# Power.net
KiCad netlist of a schematic drawn in Altium Designer
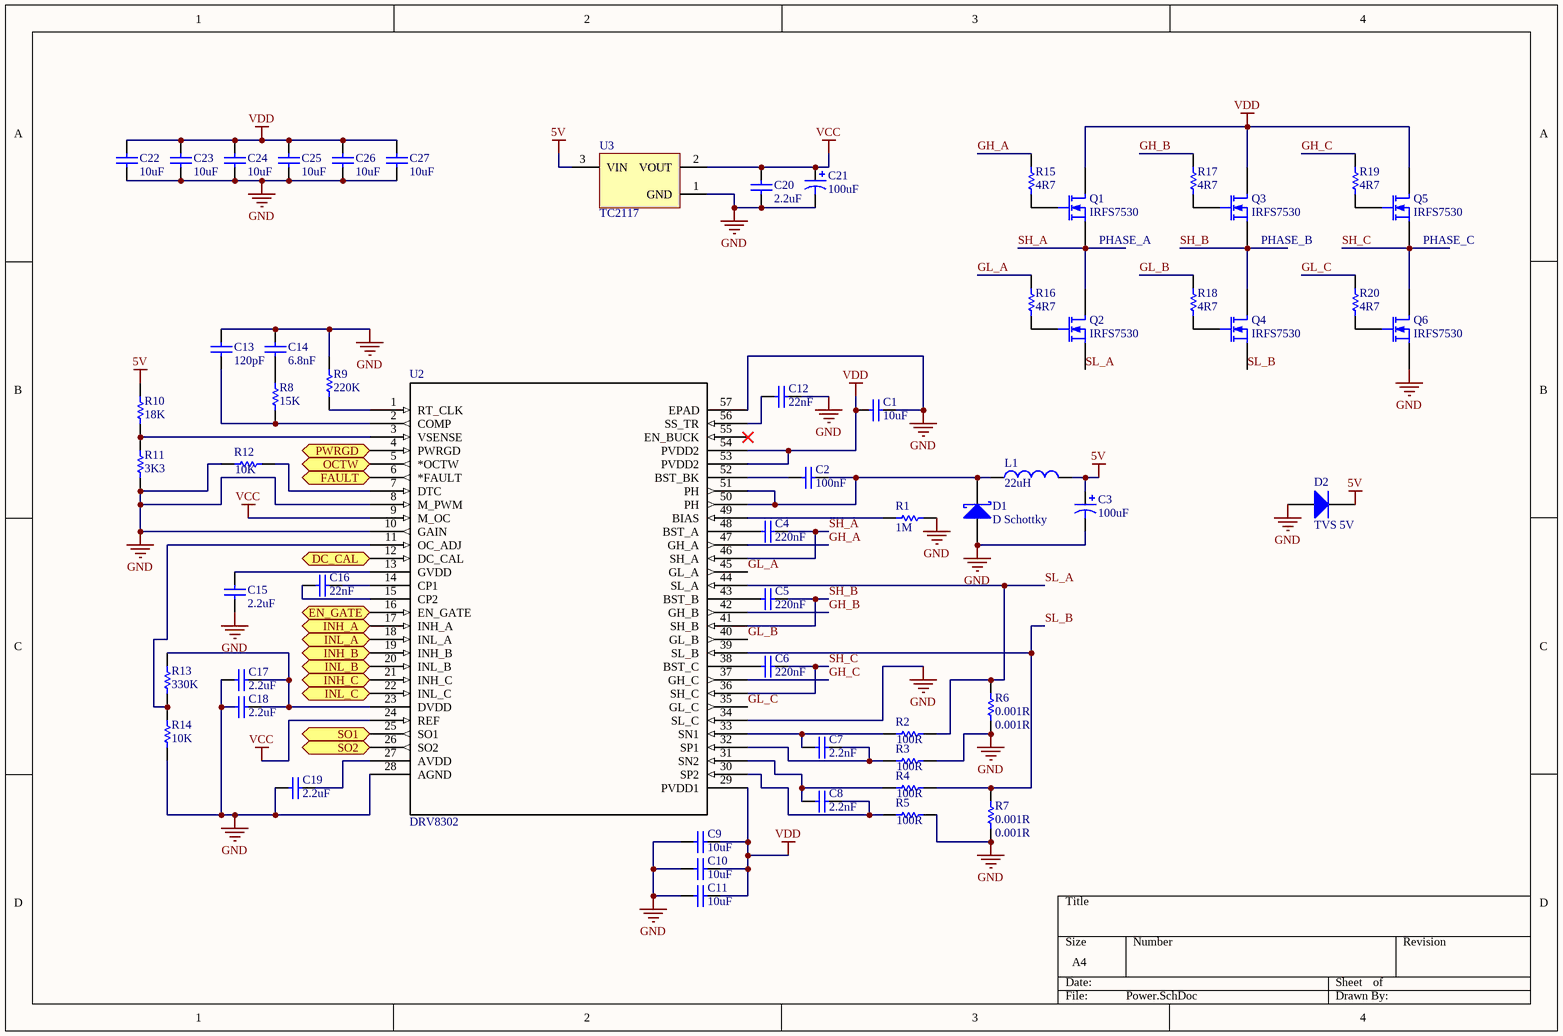
[diagram p0: Power.SchDoc]

(export (version "E")
  (design (tool "Eeschema 10.0.6"))
  (components
    (comp (ref "C1")
      (value "10uF")
      (footprint "CAPC1206(3216)190_M")
      (description "CAP 10uF 50V Â±10% 1206 (3216 Metric) Thickness 1.9mm SMD")
      (fields (field (name "TOLERANCE") "Â±10%"))
      (libsource (lib "Altium Content Vault") (part "CAP"))
    )
    (comp (ref "C2")
      (value "100nF")
      (footprint "CAPC0603(1608)100_N")
      (description "CAP 100nF 50V Â±5% 0603 (1608 Metric) Thickness 1mm SMD")
      (fields (field (name "TOLERANCE") "Â±5%"))
      (libsource (lib "Altium Content Vault") (part "CMP-1035-02591-1"))
    )
    (comp (ref "C3")
      (value "100uF")
      (footprint "AVX-CAPC7343_V")
      (description "Capacitor, Tantalum, 220uF 10% 10V MCCT-D (7343-31)")
      (fields (field (name "PARTNUMBER") "TAJD227K010R") (field (name "MANUFACTURER") "AVX"))
      (libsource (lib "Altium Content Vault") (part "CMP-0279-00002-1"))
    )
    (comp (ref "C4")
      (value "220nF")
      (footprint "CAPC0805(2012)145_M")
      (description "CAP 220nF 25V Â±5% 0805 (2012 Metric) Thickness 1.45mm SMD")
      (fields (field (name "TOLERANCE") "Â±5%"))
      (libsource (lib "Altium Content Vault") (part "CMP-1036-04540-1"))
    )
    (comp (ref "C5")
      (value "220nF")
      (footprint "CAPC0805(2012)145_M")
      (description "CAP 220nF 25V Â±5% 0805 (2012 Metric) Thickness 1.45mm SMD")
      (fields (field (name "TOLERANCE") "Â±5%"))
      (libsource (lib "Altium Content Vault") (part "CMP-1036-04540-1"))
    )
    (comp (ref "C6")
      (value "220nF")
      (footprint "CAPC0805(2012)145_M")
      (description "CAP 220nF 25V Â±5% 0805 (2012 Metric) Thickness 1.45mm SMD")
      (fields (field (name "TOLERANCE") "Â±5%"))
      (libsource (lib "Altium Content Vault") (part "CMP-1036-04540-1"))
    )
    (comp (ref "C7")
      (value "2.2nF")
      (footprint "CAPC0603(1608)100_N")
      (description "CAP 2.2nF 50V Â±1% 0603 (1608 Metric) Thickness 1mm SMD")
      (fields (field (name "TOLERANCE") "Â±1%"))
      (libsource (lib "Altium Content Vault") (part "CMP-1035-02036-1"))
    )
    (comp (ref "C8")
      (value "2.2nF")
      (footprint "CAPC0603(1608)100_N")
      (description "CAP 2.2nF 50V Â±1% 0603 (1608 Metric) Thickness 1mm SMD")
      (fields (field (name "TOLERANCE") "Â±1%"))
      (libsource (lib "Altium Content Vault") (part "CMP-1035-02036-1"))
    )
    (comp (ref "C9")
      (value "10uF")
      (footprint "CAPC1206(3216)190_M")
      (description "CAP 10uF 50V Â±10% 1206 (3216 Metric) Thickness 1.9mm SMD")
      (fields (field (name "TOLERANCE") "Â±10%"))
      (libsource (lib "Altium Content Vault") (part "CAP"))
    )
    (comp (ref "C10")
      (value "10uF")
      (footprint "CAPC1206(3216)190_M")
      (description "CAP 10uF 50V Â±10% 1206 (3216 Metric) Thickness 1.9mm SMD")
      (fields (field (name "TOLERANCE") "Â±10%"))
      (libsource (lib "Altium Content Vault") (part "CAP"))
    )
    (comp (ref "C11")
      (value "10uF")
      (footprint "CAPC1206(3216)190_M")
      (description "CAP 10uF 50V Â±10% 1206 (3216 Metric) Thickness 1.9mm SMD")
      (fields (field (name "TOLERANCE") "Â±10%"))
      (libsource (lib "Altium Content Vault") (part "CAP"))
    )
    (comp (ref "C12")
      (value "22nF")
      (footprint "CAPC0603(1608)100_N")
      (description "CAP 22nF 50V Â±5% 0603 (1608 Metric) Thickness 1mm SMD")
      (fields (field (name "TOLERANCE") "Â±5%"))
      (libsource (lib "Altium Content Vault") (part "CAP"))
    )
    (comp (ref "C13")
      (value "120pF")
      (footprint "CAPC0603(1608)100_N")
      (description "CAP 120pF 50V Â±1% 0603 (1608 Metric) Thickness 1mm SMD")
      (fields (field (name "TOLERANCE") "Â±1%"))
      (libsource (lib "Altium Content Vault") (part "CMP-1035-01317-1"))
    )
    (comp (ref "C14")
      (value "6.8nF")
      (footprint "CAPC0603(1608)100_N")
      (description "CAP 6.8nF 50V Â±1% 0603 (1608 Metric) Thickness 1mm SMD")
      (fields (field (name "TOLERANCE") "Â±1%"))
      (libsource (lib "Altium Content Vault") (part "CMP-1035-02266-1"))
    )
    (comp (ref "C15")
      (value "2.2uF")
      (footprint "CAPC0805(2012)145_N")
      (description "CAP 2.2uF 16V Â±5% 0805 (2012 Metric) Thickness 1.45mm SMD")
      (fields (field (name "TOLERANCE") "Â±5%"))
      (libsource (lib "Altium Content Vault") (part "CMP-1036-04830-1"))
    )
    (comp (ref "C16")
      (value "22nF")
      (footprint "CAPC0603(1608)100_N")
      (description "CAP 22nF 50V Â±5% 0603 (1608 Metric) Thickness 1mm SMD")
      (fields (field (name "TOLERANCE") "Â±5%"))
      (libsource (lib "Altium Content Vault") (part "CAP"))
    )
    (comp (ref "C17")
      (value "2.2uF")
      (footprint "CAPC0603(1608)55_N")
      (description "CAP 2.2uF 16V Â±10% 0603 (1608 Metric) Thickness 0.55mm SMD")
      (fields (field (name "TOLERANCE") "Â±10%"))
      (libsource (lib "Altium Content Vault") (part "CAP"))
    )
    (comp (ref "C18")
      (value "2.2uF")
      (footprint "CAPC0603(1608)55_N")
      (description "CAP 2.2uF 16V Â±10% 0603 (1608 Metric) Thickness 0.55mm SMD")
      (fields (field (name "TOLERANCE") "Â±10%"))
      (libsource (lib "Altium Content Vault") (part "CAP"))
    )
    (comp (ref "C19")
      (value "2.2uF")
      (footprint "CAPC0805(2012)145_N")
      (description "CAP 2.2uF 16V Â±5% 0805 (2012 Metric) Thickness 1.45mm SMD")
      (fields (field (name "TOLERANCE") "Â±5%"))
      (libsource (lib "Altium Content Vault") (part "CAP"))
    )
    (comp (ref "C20")
      (value "2.2uF")
      (footprint "CAPC0603(1608)55_N")
      (description "CAP 2.2uF 16V Â±10% 0603 (1608 Metric) Thickness 0.55mm SMD")
      (fields (field (name "TOLERANCE") "Â±10%"))
      (libsource (lib "Altium Content Vault") (part "CMP-1035-02762-1"))
    )
    (comp (ref "C21")
      (value "100uF")
      (footprint "AVX-CAPC7343_V")
      (description "Capacitor, Tantalum, 220uF 10% 10V MCCT-D (7343-31)")
      (fields (field (name "PARTNUMBER") "TAJD227K010R") (field (name "MANUFACTURER") "AVX"))
      (libsource (lib "Altium Content Vault") (part "CMP-0279-00002-1"))
    )
    (comp (ref "C22")
      (value "10uF")
      (footprint "CAPC1206(3216)190_M")
      (description "CAP 10uF 50V Â±10% 1206 (3216 Metric) Thickness 1.9mm SMD")
      (fields (field (name "TOLERANCE") "Â±10%"))
      (libsource (lib "Altium Content Vault") (part "CMP-1037-04982-1"))
    )
    (comp (ref "C23")
      (value "10uF")
      (footprint "CAPC1206(3216)190_M")
      (description "CAP 10uF 50V Â±10% 1206 (3216 Metric) Thickness 1.9mm SMD")
      (fields (field (name "TOLERANCE") "Â±10%"))
      (libsource (lib "Altium Content Vault") (part "CAP"))
    )
    (comp (ref "C24")
      (value "10uF")
      (footprint "CAPC1206(3216)190_M")
      (description "CAP 10uF 50V Â±10% 1206 (3216 Metric) Thickness 1.9mm SMD")
      (fields (field (name "TOLERANCE") "Â±10%"))
      (libsource (lib "Altium Content Vault") (part "CAP"))
    )
    (comp (ref "C25")
      (value "10uF")
      (footprint "CAPC1206(3216)190_M")
      (description "CAP 10uF 50V Â±10% 1206 (3216 Metric) Thickness 1.9mm SMD")
      (fields (field (name "TOLERANCE") "Â±10%"))
      (libsource (lib "Altium Content Vault") (part "CMP-1037-04982-1"))
    )
    (comp (ref "C26")
      (value "10uF")
      (footprint "CAPC1206(3216)190_M")
      (description "CAP 10uF 50V Â±10% 1206 (3216 Metric) Thickness 1.9mm SMD")
      (fields (field (name "TOLERANCE") "Â±10%"))
      (libsource (lib "Altium Content Vault") (part "CAP"))
    )
    (comp (ref "C27")
      (value "10uF")
      (footprint "CAPC1206(3216)190_M")
      (description "CAP 10uF 50V Â±10% 1206 (3216 Metric) Thickness 1.9mm SMD")
      (fields (field (name "TOLERANCE") "Â±10%"))
      (libsource (lib "Altium Content Vault") (part "CAP"))
    )
    (comp (ref "D1")
      (value "D Schottky")
      (footprint "SMB")
      (description "Schottky Diode")
      (fields (field (name "PUBLISHER") "Altium Limited"))
      (libsource (lib "Miscellaneous Devices") (part "D Schottky"))
    )
    (comp (ref "D2")
      (value "TVS 5V")
      (footprint "VISH-DO-214AC-2_N")
      (fields
        (field (name "PARTNUMBER") "SMAJ5.0A-E3/61")
        (field (name "MANUFACTURER") "Vishay Semiconductor")
      )
      (libsource (lib "Altium Content Vault") (part "CMP-0548-00235-1"))
    )
    (comp (ref "L1")
      (value "22uH")
      (footprint "SDR0805-180ML")
      (description "Inductor")
      (fields (field (name "Comment") "SDR0805-180ML") (field (name "PUBLISHER") "Altium Limited"))
      (libsource (lib "Components") (part "SDR0805-180ML"))
    )
    (comp (ref "Q1")
      (value "IRFS7530")
      (footprint "DPAK127P1525X483-7N")
      (description "N-Channel MOSFET")
      (fields (field (name "PUBLISHER") "Altium Limited"))
      (libsource (lib "Components") (part "IRFS7530"))
    )
    (comp (ref "Q2")
      (value "IRFS7530")
      (footprint "DPAK127P1525X483-7N")
      (description "N-Channel MOSFET")
      (fields (field (name "PUBLISHER") "Altium Limited"))
      (libsource (lib "Components") (part "IRFS7530"))
    )
    (comp (ref "Q3")
      (value "IRFS7530")
      (footprint "DPAK127P1525X483-7N")
      (description "N-Channel MOSFET")
      (fields (field (name "PUBLISHER") "Altium Limited"))
      (libsource (lib "Components") (part "IRFS7530"))
    )
    (comp (ref "Q4")
      (value "IRFS7530")
      (footprint "DPAK127P1525X483-7N")
      (description "N-Channel MOSFET")
      (fields (field (name "PUBLISHER") "Altium Limited"))
      (libsource (lib "Components") (part "IRFS7530"))
    )
    (comp (ref "Q5")
      (value "IRFS7530")
      (footprint "DPAK127P1525X483-7N")
      (description "N-Channel MOSFET")
      (fields (field (name "PUBLISHER") "Altium Limited"))
      (libsource (lib "Components") (part "IRFS7530"))
    )
    (comp (ref "Q6")
      (value "IRFS7530")
      (footprint "DPAK127P1525X483-7N")
      (description "N-Channel MOSFET")
      (fields (field (name "PUBLISHER") "Altium Limited"))
      (libsource (lib "Components") (part "IRFS7530"))
    )
    (comp (ref "R1")
      (value "1M")
      (footprint "RESC0603(1608)_N")
      (description "1M 0.1W 5% 0603 (1608 Metric)  SMD")
      (fields (field (name "POWER") "0.1 W") (field (name "TOLERANCE") "5 %"))
      (libsource (lib "Altium Content Vault") (part "CMP-1012-00146-1"))
    )
    (comp (ref "R2")
      (value "100R")
      (footprint "RESC0603(1608)_N")
      (description "100R 0.1W 5% 0603 (1608 Metric)  SMD")
      (fields (field (name "TOLERANCE") "5 %") (field (name "POWER") "0.1 W"))
      (libsource (lib "Altium Content Vault") (part "CMP-1012-00050-1"))
    )
    (comp (ref "R3")
      (value "100R")
      (footprint "RESC0603(1608)_N")
      (description "100R 0.1W 5% 0603 (1608 Metric)  SMD")
      (fields (field (name "TOLERANCE") "5 %") (field (name "POWER") "0.1 W"))
      (libsource (lib "Altium Content Vault") (part "CMP-1012-00050-1"))
    )
    (comp (ref "R4")
      (value "100R")
      (footprint "RESC0603(1608)_N")
      (description "100R 0.1W 5% 0603 (1608 Metric)  SMD")
      (fields (field (name "TOLERANCE") "5 %") (field (name "POWER") "0.1 W"))
      (libsource (lib "Altium Content Vault") (part "CMP-1012-00050-1"))
    )
    (comp (ref "R5")
      (value "100R")
      (footprint "RESC0603(1608)_N")
      (description "100R 0.1W 5% 0603 (1608 Metric)  SMD")
      (fields (field (name "TOLERANCE") "5 %") (field (name "POWER") "0.1 W"))
      (libsource (lib "Altium Content Vault") (part "CMP-1012-00050-1"))
    )
    (comp (ref "R6")
      (value "0.001R")
      (footprint "Shunt")
      (description "Resistor")
      (fields (field (name "ALTIUM_VALUE") "0.001R") (field (name "PUBLISHER") "Altium Limited"))
      (libsource (lib "Components") (part "Shunt"))
    )
    (comp (ref "R7")
      (value "0.001R")
      (footprint "Shunt")
      (description "Resistor")
      (fields (field (name "ALTIUM_VALUE") "0.001R") (field (name "PUBLISHER") "Altium Limited"))
      (libsource (lib "Components") (part "Shunt"))
    )
    (comp (ref "R8")
      (value "15K")
      (footprint "RESC0603(1608)_N")
      (description "15K 0.1W 5% 0603 (1608 Metric)  SMD")
      (fields (field (name "POWER") "0.1 W") (field (name "TOLERANCE") "5 %"))
      (libsource (lib "Altium Content Vault") (part "CMP-1012-00102-1"))
    )
    (comp (ref "R9")
      (value "220K")
      (footprint "RESC0603(1608)_N")
      (description "220K 0.1W 5% 0603 (1608 Metric)  SMD")
      (fields (field (name "TOLERANCE") "5 %") (field (name "POWER") "0.1 W"))
      (libsource (lib "Altium Content Vault") (part "CMP-1012-00130-1"))
    )
    (comp (ref "R10")
      (value "18K")
      (footprint "RESC0603(1608)_N")
      (description "18K 0.1W 5% 0603 (1608 Metric)  SMD")
      (fields (field (name "POWER") "0.1 W") (field (name "TOLERANCE") "5 %"))
      (libsource (lib "Altium Content Vault") (part "CMP-1012-00104-1"))
    )
    (comp (ref "R11")
      (value "3K3")
      (footprint "RESC0603(1608)_N")
      (description "3K3 0.1W 5% 0603 (1608 Metric)  SMD")
      (fields (field (name "TOLERANCE") "5 %") (field (name "POWER") "0.1 W"))
      (libsource (lib "Altium Content Vault") (part "CMP-1012-00086-1"))
    )
    (comp (ref "R12")
      (value "10K")
      (footprint "RESC0603(1608)_N")
      (description "10K 0.1W 5% 0603 (1608 Metric)  SMD")
      (fields (field (name "TOLERANCE") "5 %") (field (name "POWER") "0.1 W"))
      (libsource (lib "Altium Content Vault") (part "CMP-1012-00098-1"))
    )
    (comp (ref "R13")
      (value "330K")
      (footprint "RESC0603(1608)_N")
      (description "330K 0.1W 5% 0603 (1608 Metric)  SMD")
      (fields (field (name "POWER") "0.1 W") (field (name "TOLERANCE") "5 %"))
      (libsource (lib "Altium Content Vault") (part "CMP-1012-00134-1"))
    )
    (comp (ref "R14")
      (value "10K")
      (footprint "RESC0603(1608)_N")
      (description "10K 0.1W 5% 0603 (1608 Metric)  SMD")
      (fields (field (name "TOLERANCE") "5 %") (field (name "POWER") "0.1 W"))
      (libsource (lib "Altium Content Vault") (part "CMP-1012-00098-1"))
    )
    (comp (ref "R15")
      (value "4R7")
      (footprint "RESC0603(1608)_N")
      (description "4R7 0.1W 5% 0603 (1608 Metric)  SMD")
      (fields (field (name "POWER") "0.1 W") (field (name "TOLERANCE") "5 %"))
      (libsource (lib "Altium Content Vault") (part "CMP-1012-00018-1"))
    )
    (comp (ref "R16")
      (value "4R7")
      (footprint "RESC0603(1608)_N")
      (description "4R7 0.1W 5% 0603 (1608 Metric)  SMD")
      (fields (field (name "POWER") "0.1 W") (field (name "TOLERANCE") "5 %"))
      (libsource (lib "Altium Content Vault") (part "CMP-1012-00018-1"))
    )
    (comp (ref "R17")
      (value "4R7")
      (footprint "RESC0603(1608)_M")
      (description "4R7 0.1W 5% 0603 (1608 Metric)  SMD")
      (fields (field (name "POWER") "0.1 W") (field (name "TOLERANCE") "5 %"))
      (libsource (lib "Altium Content Vault") (part "RES"))
    )
    (comp (ref "R18")
      (value "4R7")
      (footprint "RESC0603(1608)_N")
      (description "4R7 0.1W 5% 0603 (1608 Metric)  SMD")
      (fields (field (name "POWER") "0.1 W") (field (name "TOLERANCE") "5 %"))
      (libsource (lib "Altium Content Vault") (part "CMP-1012-00018-1"))
    )
    (comp (ref "R19")
      (value "4R7")
      (footprint "RESC0603(1608)_N")
      (description "4R7 0.1W 5% 0603 (1608 Metric)  SMD")
      (fields (field (name "POWER") "0.1 W") (field (name "TOLERANCE") "5 %"))
      (libsource (lib "Altium Content Vault") (part "CMP-1012-00018-1"))
    )
    (comp (ref "R20")
      (value "4R7")
      (footprint "RESC0603(1608)_N")
      (description "4R7 0.1W 5% 0603 (1608 Metric)  SMD")
      (fields (field (name "POWER") "0.1 W") (field (name "TOLERANCE") "5 %"))
      (libsource (lib "Altium Content Vault") (part "CMP-1012-00018-1"))
    )
    (comp (ref "U2")
      (value "DRV8302")
      (footprint "DCA56_6P35X3P61")
      (description "Imported")
      (fields
        (field (name "MANUFACTURER") "Texas Instruments")
        (field (name "MANUFACTURER_PART_NUMBER") "drv8302_dca_56")
      )
      (libsource (lib "DRV8302") (part "DRV8302_DCA_56"))
    )
    (comp (ref "U3")
      (value "TC2117")
      (footprint "SOT-223-DB3_M")
      (libsource (lib "Components") (part "PM-LINEREG-TC2117-IL4"))
    )
  )
  (nets
    (net (code "1") (name "/DC_CAL") (class "Default")
      (node (ref "U2") (pin "12") (pinfunction "DC_CAL_12") (pintype "input"))
    )
    (net (code "2") (name "/EN_GATE") (class "Default")
      (node (ref "U2") (pin "16") (pinfunction "EN_GATE_16") (pintype "input"))
    )
    (net (code "3") (name "/FAULT") (class "Default")
      (node (ref "U2") (pin "6") (pinfunction "*FAULT_6") (pintype "output"))
    )
    (net (code "4") (name "/GH_A") (class "Default")
      (node (ref "R15") (pin "2") (pinfunction "2_2") (pintype "passive"))
      (node (ref "U2") (pin "47") (pinfunction "GH_A_47") (pintype "output"))
    )
    (net (code "5") (name "/GH_B") (class "Default")
      (node (ref "R17") (pin "2") (pinfunction "2_2") (pintype "passive"))
      (node (ref "U2") (pin "42") (pinfunction "GH_B_42") (pintype "output"))
    )
    (net (code "6") (name "/GH_C") (class "Default")
      (node (ref "R19") (pin "2") (pinfunction "2_2") (pintype "passive"))
      (node (ref "U2") (pin "37") (pinfunction "GH_C_37") (pintype "output"))
    )
    (net (code "7") (name "/GL_A") (class "Default")
      (node (ref "R16") (pin "2") (pinfunction "2_2") (pintype "passive"))
      (node (ref "U2") (pin "45") (pinfunction "GL_A_45") (pintype "output"))
    )
    (net (code "8") (name "/GL_B") (class "Default")
      (node (ref "R18") (pin "2") (pinfunction "2_2") (pintype "passive"))
      (node (ref "U2") (pin "40") (pinfunction "GL_B_40") (pintype "output"))
    )
    (net (code "9") (name "/GL_C") (class "Default")
      (node (ref "R20") (pin "2") (pinfunction "2_2") (pintype "passive"))
      (node (ref "U2") (pin "35") (pinfunction "GL_C_35") (pintype "output"))
    )
    (net (code "10") (name "/INH_A") (class "Default")
      (node (ref "U2") (pin "17") (pinfunction "INH_A_17") (pintype "input"))
    )
    (net (code "11") (name "/INH_B") (class "Default")
      (node (ref "U2") (pin "19") (pinfunction "INH_B_19") (pintype "input"))
    )
    (net (code "12") (name "/INH_C") (class "Default")
      (node (ref "U2") (pin "21") (pinfunction "INH_C_21") (pintype "input"))
    )
    (net (code "13") (name "/INL_A") (class "Default")
      (node (ref "U2") (pin "18") (pinfunction "INL_A_18") (pintype "input"))
    )
    (net (code "14") (name "/INL_B") (class "Default")
      (node (ref "U2") (pin "20") (pinfunction "INL_B_20") (pintype "input"))
    )
    (net (code "15") (name "/INL_C") (class "Default")
      (node (ref "U2") (pin "22") (pinfunction "INL_C_22") (pintype "input"))
    )
    (net (code "16") (name "/OCTW") (class "Default")
      (node (ref "U2") (pin "5") (pinfunction "*OCTW_5") (pintype "output"))
    )
    (net (code "17") (name "/PWRGD") (class "Default")
      (node (ref "U2") (pin "4") (pinfunction "PWRGD_4") (pintype "input"))
    )
    (net (code "18") (name "/SH_A") (class "Default")
      (node (ref "C4") (pin "2") (pinfunction "2_2") (pintype "passive"))
      (node (ref "Q1") (pin "3") (pinfunction "S_3") (pintype "passive"))
      (node (ref "Q2") (pin "1") (pinfunction "D_1") (pintype "passive"))
      (node (ref "U2") (pin "46") (pinfunction "SH_A_46") (pintype "input"))
    )
    (net (code "19") (name "/SH_B") (class "Default")
      (node (ref "C5") (pin "2") (pinfunction "2_2") (pintype "passive"))
      (node (ref "Q3") (pin "3") (pinfunction "S_3") (pintype "passive"))
      (node (ref "Q4") (pin "1") (pinfunction "D_1") (pintype "passive"))
      (node (ref "U2") (pin "41") (pinfunction "SH_B_41") (pintype "input"))
    )
    (net (code "20") (name "/SH_C") (class "Default")
      (node (ref "C6") (pin "2") (pinfunction "2_2") (pintype "passive"))
      (node (ref "Q5") (pin "3") (pinfunction "S_3") (pintype "passive"))
      (node (ref "Q6") (pin "1") (pinfunction "D_1") (pintype "passive"))
      (node (ref "U2") (pin "36") (pinfunction "SH_C_36") (pintype "input"))
    )
    (net (code "21") (name "/SL_A") (class "Default")
      (node (ref "Q2") (pin "3") (pinfunction "S_3") (pintype "passive"))
      (node (ref "R2") (pin "2") (pinfunction "2_2") (pintype "passive"))
      (node (ref "R6") (pin "2") (pinfunction "2_2") (pintype "passive"))
      (node (ref "U2") (pin "44") (pinfunction "SL_A_44") (pintype "input"))
    )
    (net (code "22") (name "/SL_B") (class "Default")
      (node (ref "Q4") (pin "3") (pinfunction "S_3") (pintype "passive"))
      (node (ref "R4") (pin "2") (pinfunction "2_2") (pintype "passive"))
      (node (ref "R7") (pin "2") (pinfunction "2_2") (pintype "passive"))
      (node (ref "U2") (pin "39") (pinfunction "SL_B_39") (pintype "input"))
    )
    (net (code "23") (name "/SO1") (class "Default")
      (node (ref "U2") (pin "25") (pinfunction "SO1_25") (pintype "output"))
    )
    (net (code "24") (name "/SO2") (class "Default")
      (node (ref "U2") (pin "26") (pinfunction "SO2_26") (pintype "output"))
    )
    (net (code "25") (name "5V") (class "Default")
      (node (ref "C3") (pin "1") (pinfunction "1_1") (pintype "passive"))
      (node (ref "D2") (pin "1") (pinfunction "K_1") (pintype "passive"))
      (node (ref "L1") (pin "2") (pinfunction "2_2") (pintype "passive"))
      (node (ref "R10") (pin "1") (pinfunction "1_1") (pintype "passive"))
      (node (ref "U3") (pin "3") (pinfunction "VIN_3") (pintype "power_in"))
    )
    (net (code "26") (name "GND") (class "Default")
      (node (ref "C1") (pin "2") (pinfunction "2_2") (pintype "passive"))
      (node (ref "C10") (pin "1") (pinfunction "1_1") (pintype "passive"))
      (node (ref "C11") (pin "1") (pinfunction "1_1") (pintype "passive"))
      (node (ref "C12") (pin "2") (pinfunction "2_2") (pintype "passive"))
      (node (ref "C13") (pin "1") (pinfunction "1_1") (pintype "passive"))
      (node (ref "C14") (pin "1") (pinfunction "1_1") (pintype "passive"))
      (node (ref "C15") (pin "2") (pinfunction "2_2") (pintype "passive"))
      (node (ref "C17") (pin "1") (pinfunction "1_1") (pintype "passive"))
      (node (ref "C18") (pin "1") (pinfunction "1_1") (pintype "passive"))
      (node (ref "C19") (pin "1") (pinfunction "1_1") (pintype "passive"))
      (node (ref "C20") (pin "2") (pinfunction "2_2") (pintype "passive"))
      (node (ref "C21") (pin "2") (pinfunction "2_2") (pintype "passive"))
      (node (ref "C22") (pin "1") (pinfunction "1_1") (pintype "passive"))
      (node (ref "C23") (pin "1") (pinfunction "1_1") (pintype "passive"))
      (node (ref "C24") (pin "1") (pinfunction "1_1") (pintype "passive"))
      (node (ref "C25") (pin "1") (pinfunction "1_1") (pintype "passive"))
      (node (ref "C26") (pin "1") (pinfunction "1_1") (pintype "passive"))
      (node (ref "C27") (pin "1") (pinfunction "1_1") (pintype "passive"))
      (node (ref "C3") (pin "2") (pinfunction "2_2") (pintype "passive"))
      (node (ref "C9") (pin "1") (pinfunction "1_1") (pintype "passive"))
      (node (ref "D1") (pin "1") (pinfunction "A_1") (pintype "passive"))
      (node (ref "D2") (pin "2") (pinfunction "A_2") (pintype "passive"))
      (node (ref "Q6") (pin "3") (pinfunction "S_3") (pintype "passive"))
      (node (ref "R1") (pin "2") (pinfunction "2_2") (pintype "passive"))
      (node (ref "R11") (pin "2") (pinfunction "2_2") (pintype "passive"))
      (node (ref "R12") (pin "1") (pinfunction "1_1") (pintype "passive"))
      (node (ref "R14") (pin "2") (pinfunction "2_2") (pintype "passive"))
      (node (ref "R3") (pin "2") (pinfunction "2_2") (pintype "passive"))
      (node (ref "R5") (pin "2") (pinfunction "2_2") (pintype "passive"))
      (node (ref "R6") (pin "1") (pinfunction "1_1") (pintype "passive"))
      (node (ref "R7") (pin "1") (pinfunction "1_1") (pintype "passive"))
      (node (ref "R9") (pin "1") (pinfunction "1_1") (pintype "passive"))
      (node (ref "U2") (pin "10") (pinfunction "GAIN_10") (pintype "output"))
      (node (ref "U2") (pin "28") (pinfunction "AGND_28") (pintype "power_in"))
      (node (ref "U2") (pin "34") (pinfunction "SL_C_34") (pintype "input"))
      (node (ref "U2") (pin "57") (pinfunction "EPAD_57") (pintype "passive"))
      (node (ref "U2") (pin "8") (pinfunction "M_PWM_8") (pintype "input"))
      (node (ref "U3") (pin "1") (pinfunction "GND_1") (pintype "power_in"))
    )
    (net (code "27") (name "Net-(C14-Pad2)") (class "Default")
      (node (ref "C14") (pin "2") (pinfunction "2_2") (pintype "passive"))
      (node (ref "R8") (pin "1") (pinfunction "1_1") (pintype "passive"))
    )
    (net (code "28") (name "Net-(D1-K)") (class "Default")
      (node (ref "C2") (pin "2") (pinfunction "2_2") (pintype "passive"))
      (node (ref "D1") (pin "2") (pinfunction "K_2") (pintype "passive"))
      (node (ref "L1") (pin "1") (pinfunction "1_1") (pintype "passive"))
      (node (ref "U2") (pin "50") (pinfunction "PH_50") (pintype "output"))
      (node (ref "U2") (pin "51") (pinfunction "PH_51") (pintype "output"))
    )
    (net (code "29") (name "Net-(Q1-G)") (class "Default")
      (node (ref "Q1") (pin "2") (pinfunction "G_2") (pintype "passive"))
      (node (ref "R15") (pin "1") (pinfunction "1_1") (pintype "passive"))
    )
    (net (code "30") (name "Net-(Q2-G)") (class "Default")
      (node (ref "Q2") (pin "2") (pinfunction "G_2") (pintype "passive"))
      (node (ref "R16") (pin "1") (pinfunction "1_1") (pintype "passive"))
    )
    (net (code "31") (name "Net-(Q3-G)") (class "Default")
      (node (ref "Q3") (pin "2") (pinfunction "G_2") (pintype "passive"))
      (node (ref "R17") (pin "1") (pinfunction "1_1") (pintype "passive"))
    )
    (net (code "32") (name "Net-(Q4-G)") (class "Default")
      (node (ref "Q4") (pin "2") (pinfunction "G_2") (pintype "passive"))
      (node (ref "R18") (pin "1") (pinfunction "1_1") (pintype "passive"))
    )
    (net (code "33") (name "Net-(Q5-G)") (class "Default")
      (node (ref "Q5") (pin "2") (pinfunction "G_2") (pintype "passive"))
      (node (ref "R19") (pin "1") (pinfunction "1_1") (pintype "passive"))
    )
    (net (code "34") (name "Net-(Q6-G)") (class "Default")
      (node (ref "Q6") (pin "2") (pinfunction "G_2") (pintype "passive"))
      (node (ref "R20") (pin "1") (pinfunction "1_1") (pintype "passive"))
    )
    (net (code "35") (name "Net-(U2-AVDD)") (class "Default")
      (node (ref "C19") (pin "2") (pinfunction "2_2") (pintype "passive"))
      (node (ref "U2") (pin "27") (pinfunction "AVDD_27") (pintype "power_in"))
    )
    (net (code "36") (name "Net-(U2-BIAS)") (class "Default")
      (node (ref "R1") (pin "1") (pinfunction "1_1") (pintype "passive"))
      (node (ref "U2") (pin "49") (pinfunction "BIAS_49") (pintype "input"))
    )
    (net (code "37") (name "Net-(U2-BST_A)") (class "Default")
      (node (ref "C4") (pin "1") (pinfunction "1_1") (pintype "passive"))
      (node (ref "U2") (pin "48") (pinfunction "BST_A_48") (pintype "power_in"))
    )
    (net (code "38") (name "Net-(U2-BST_B)") (class "Default")
      (node (ref "C5") (pin "1") (pinfunction "1_1") (pintype "passive"))
      (node (ref "U2") (pin "43") (pinfunction "BST_B_43") (pintype "power_in"))
    )
    (net (code "39") (name "Net-(U2-BST_BK)") (class "Default")
      (node (ref "C2") (pin "1") (pinfunction "1_1") (pintype "passive"))
      (node (ref "U2") (pin "52") (pinfunction "BST_BK_52") (pintype "power_in"))
    )
    (net (code "40") (name "Net-(U2-BST_C)") (class "Default")
      (node (ref "C6") (pin "1") (pinfunction "1_1") (pintype "passive"))
      (node (ref "U2") (pin "38") (pinfunction "BST_C_38") (pintype "power_in"))
    )
    (net (code "41") (name "Net-(U2-COMP)") (class "Default")
      (node (ref "C13") (pin "2") (pinfunction "2_2") (pintype "passive"))
      (node (ref "R8") (pin "2") (pinfunction "2_2") (pintype "passive"))
      (node (ref "U2") (pin "2") (pinfunction "COMP_2") (pintype "output"))
    )
    (net (code "42") (name "Net-(U2-CP1)") (class "Default")
      (node (ref "C16") (pin "2") (pinfunction "2_2") (pintype "passive"))
      (node (ref "U2") (pin "14") (pinfunction "CP1_14") (pintype "power_in"))
    )
    (net (code "43") (name "Net-(U2-CP2)") (class "Default")
      (node (ref "C16") (pin "1") (pinfunction "1_1") (pintype "passive"))
      (node (ref "U2") (pin "15") (pinfunction "CP2_15") (pintype "power_in"))
    )
    (net (code "44") (name "Net-(U2-DTC)") (class "Default")
      (node (ref "R12") (pin "2") (pinfunction "2_2") (pintype "passive"))
      (node (ref "U2") (pin "7") (pinfunction "DTC_7") (pintype "input"))
    )
    (net (code "45") (name "Net-(U2-DVDD)") (class "Default")
      (node (ref "C17") (pin "2") (pinfunction "2_2") (pintype "passive"))
      (node (ref "C18") (pin "2") (pinfunction "2_2") (pintype "passive"))
      (node (ref "R13") (pin "1") (pinfunction "1_1") (pintype "passive"))
      (node (ref "U2") (pin "23") (pinfunction "DVDD_23") (pintype "power_in"))
    )
    (net (code "46") (name "Net-(U2-GVDD)") (class "Default")
      (node (ref "C15") (pin "1") (pinfunction "1_1") (pintype "passive"))
      (node (ref "U2") (pin "13") (pinfunction "GVDD_13") (pintype "power_in"))
    )
    (net (code "47") (name "Net-(U2-OC_ADJ)") (class "Default")
      (node (ref "R13") (pin "2") (pinfunction "2_2") (pintype "passive"))
      (node (ref "R14") (pin "1") (pinfunction "1_1") (pintype "passive"))
      (node (ref "U2") (pin "11") (pinfunction "OC_ADJ_11") (pintype "input"))
    )
    (net (code "48") (name "Net-(U2-RT_CLK)") (class "Default")
      (node (ref "R9") (pin "2") (pinfunction "2_2") (pintype "passive"))
      (node (ref "U2") (pin "1") (pinfunction "RT_CLK_1") (pintype "input"))
    )
    (net (code "49") (name "Net-(U2-SN1)") (class "Default")
      (node (ref "C7") (pin "1") (pinfunction "1_1") (pintype "passive"))
      (node (ref "R2") (pin "1") (pinfunction "1_1") (pintype "passive"))
      (node (ref "U2") (pin "33") (pinfunction "SN1_33") (pintype "input"))
    )
    (net (code "50") (name "Net-(U2-SN2)") (class "Default")
      (node (ref "C8") (pin "1") (pinfunction "1_1") (pintype "passive"))
      (node (ref "R4") (pin "1") (pinfunction "1_1") (pintype "passive"))
      (node (ref "U2") (pin "31") (pinfunction "SN2_31") (pintype "input"))
    )
    (net (code "51") (name "Net-(U2-SP1)") (class "Default")
      (node (ref "C7") (pin "2") (pinfunction "2_2") (pintype "passive"))
      (node (ref "R3") (pin "1") (pinfunction "1_1") (pintype "passive"))
      (node (ref "U2") (pin "32") (pinfunction "SP1_32") (pintype "input"))
    )
    (net (code "52") (name "Net-(U2-SP2)") (class "Default")
      (node (ref "C8") (pin "2") (pinfunction "2_2") (pintype "passive"))
      (node (ref "R5") (pin "1") (pinfunction "1_1") (pintype "passive"))
      (node (ref "U2") (pin "30") (pinfunction "SP2_30") (pintype "input"))
    )
    (net (code "53") (name "Net-(U2-SS_TR)") (class "Default")
      (node (ref "C12") (pin "1") (pinfunction "1_1") (pintype "passive"))
      (node (ref "U2") (pin "56") (pinfunction "SS_TR_56") (pintype "input"))
    )
    (net (code "54") (name "Net-(U2-VSENSE)") (class "Default")
      (node (ref "R10") (pin "2") (pinfunction "2_2") (pintype "passive"))
      (node (ref "R11") (pin "1") (pinfunction "1_1") (pintype "passive"))
      (node (ref "U2") (pin "3") (pinfunction "VSENSE_3") (pintype "input"))
    )
    (net (code "55") (name "VCC") (class "Default")
      (node (ref "C20") (pin "1") (pinfunction "1_1") (pintype "passive"))
      (node (ref "C21") (pin "1") (pinfunction "1_1") (pintype "passive"))
      (node (ref "U2") (pin "24") (pinfunction "REF_24") (pintype "input"))
      (node (ref "U2") (pin "9") (pinfunction "M_OC_9") (pintype "input"))
      (node (ref "U3") (pin "2") (pinfunction "VOUT_2") (pintype "power_in"))
    )
    (net (code "56") (name "VDD") (class "Default")
      (node (ref "C1") (pin "1") (pinfunction "1_1") (pintype "passive"))
      (node (ref "C10") (pin "2") (pinfunction "2_2") (pintype "passive"))
      (node (ref "C11") (pin "2") (pinfunction "2_2") (pintype "passive"))
      (node (ref "C22") (pin "2") (pinfunction "2_2") (pintype "passive"))
      (node (ref "C23") (pin "2") (pinfunction "2_2") (pintype "passive"))
      (node (ref "C24") (pin "2") (pinfunction "2_2") (pintype "passive"))
      (node (ref "C25") (pin "2") (pinfunction "2_2") (pintype "passive"))
      (node (ref "C26") (pin "2") (pinfunction "2_2") (pintype "passive"))
      (node (ref "C27") (pin "2") (pinfunction "2_2") (pintype "passive"))
      (node (ref "C9") (pin "2") (pinfunction "2_2") (pintype "passive"))
      (node (ref "Q1") (pin "1") (pinfunction "D_1") (pintype "passive"))
      (node (ref "Q3") (pin "1") (pinfunction "D_1") (pintype "passive"))
      (node (ref "Q5") (pin "1") (pinfunction "D_1") (pintype "passive"))
      (node (ref "U2") (pin "29") (pinfunction "PVDD1_29") (pintype "power_in"))
      (node (ref "U2") (pin "53") (pinfunction "PVDD2_53") (pintype "power_in"))
      (node (ref "U2") (pin "54") (pinfunction "PVDD2_54") (pintype "power_in"))
    )
    (net (code "57") (name "unconnected-(U2-EN_BUCK-Pad55)") (class "Default")
      (node (ref "U2") (pin "55") (pinfunction "EN_BUCK_55") (pintype "input+no_connect"))
    )
  )
)
